# DCF_ALIM_SWITCH_RESET.net
KiCad netlist of a schematic drawn in Altium Designer
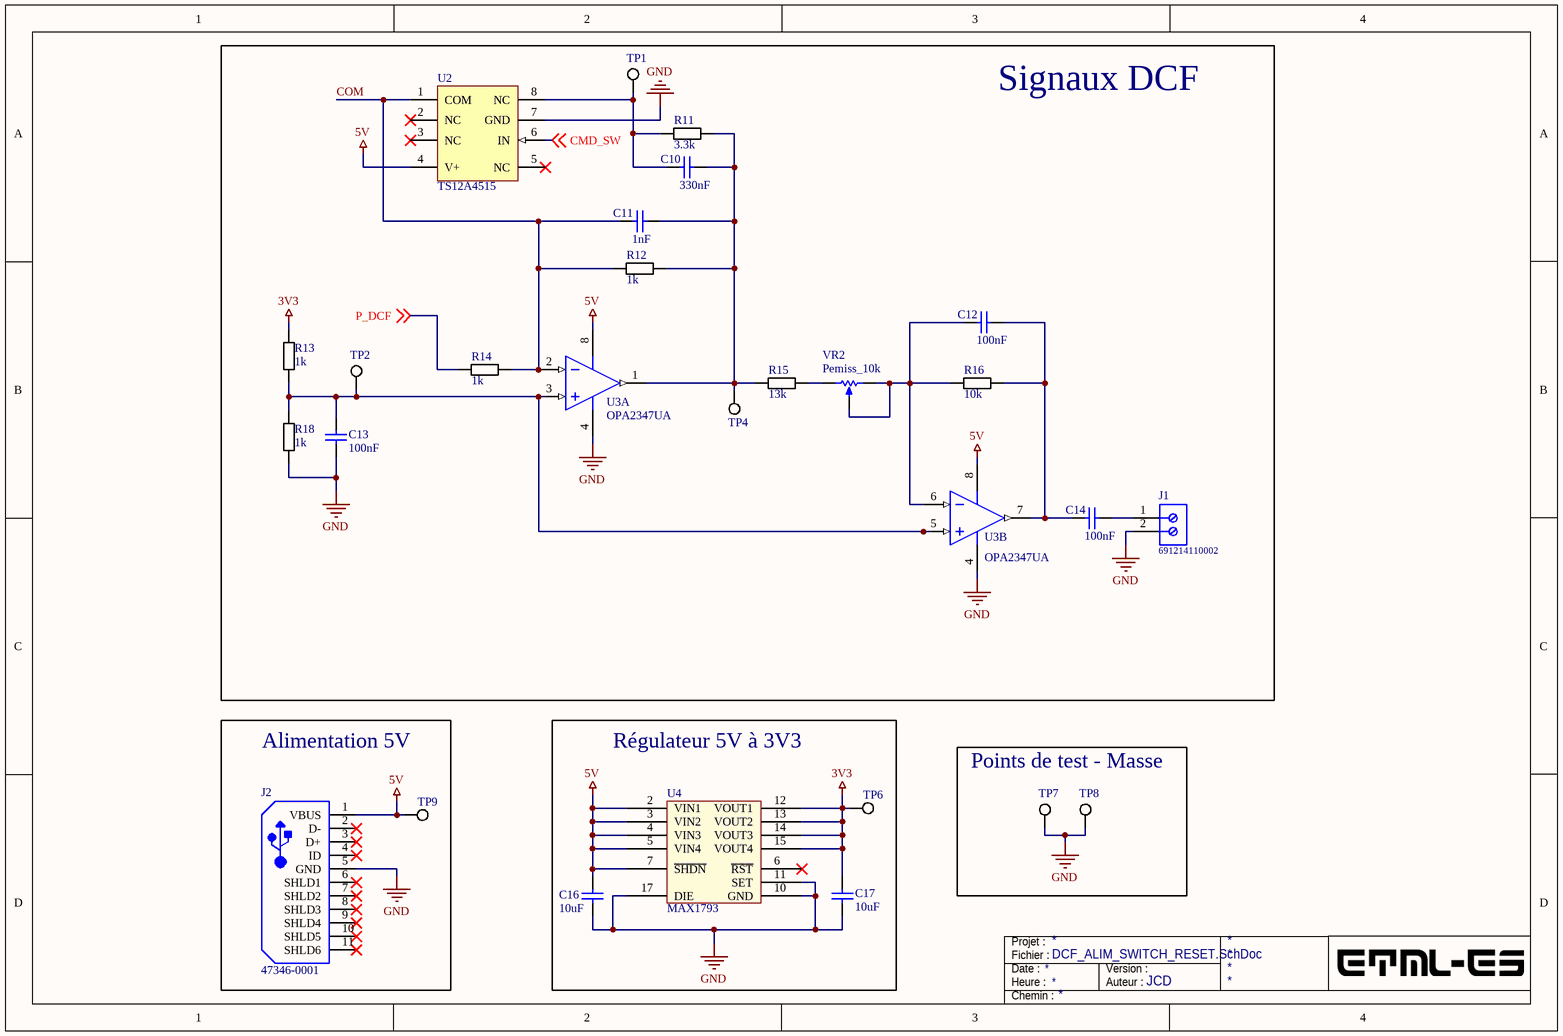
[diagram p0: DCF_ALIM_SWITCH_RESET.SchDoc]

(export (version "E")
  (design (tool "Eeschema 10.0.6"))
  (components
    (comp (ref "C10")
      (value "330nF")
      (footprint "C0805")
      (description "Capacitor")
      (fields (field (name "PUBLISHER") "Altium Limited"))
      (libsource (lib "Miscellaneous Devices") (part "Cap"))
    )
    (comp (ref "C11")
      (value "1nF")
      (footprint "C0805")
      (description "Capacitor")
      (fields (field (name "Comment") "100nF") (field (name "PUBLISHER") "Altium Limited"))
      (libsource (lib "Miscellaneous Devices") (part "Cap"))
    )
    (comp (ref "C12")
      (value "100nF")
      (footprint "C0805")
      (description "Capacitor")
      (fields (field (name "PUBLISHER") "Altium Limited"))
      (libsource (lib "Miscellaneous Devices") (part "Cap"))
    )
    (comp (ref "C13")
      (value "100nF")
      (footprint "C0805")
      (description "Capacitor")
      (fields (field (name "PUBLISHER") "Altium Limited"))
      (libsource (lib "Miscellaneous Devices") (part "Cap"))
    )
    (comp (ref "C14")
      (value "100nF")
      (footprint "C0805")
      (description "Capacitor")
      (fields (field (name "PUBLISHER") "Altium Limited"))
      (libsource (lib "Miscellaneous Devices") (part "Cap"))
    )
    (comp (ref "C16")
      (value "10uF")
      (footprint "C0805")
      (description "Capacitor")
      (fields (field (name "PUBLISHER") "Altium Limited"))
      (libsource (lib "Miscellaneous Devices") (part "Cap"))
    )
    (comp (ref "C17")
      (value "10uF")
      (footprint "C0805")
      (description "Capacitor")
      (fields (field (name "PUBLISHER") "Altium Limited"))
      (libsource (lib "Miscellaneous Devices") (part "Cap"))
    )
    (comp (ref "J1")
      (value "691214110002")
      (footprint "691214110002")
      (description "Serie 2141 - 3.50 mm Horizontal Entry Modular with Rising Cage Clamp WR-TBL, 2 pin")
      (fields (field (name "PUBLISHER") "Wurth Elektronik"))
      (libsource (lib "ALTIUM-RISING_CAGE_CLAMP_CONTBL2-rev18b") (part "691214110002"))
    )
    (comp (ref "J2")
      (value "47346-0001")
      (footprint "MOLX-47346-0001-5_V")
      (description "Micro-USB B Receptacle with Flange, -30 to 85 degC, 5-Pin SMD, RoHS, Tape and Reel")
      (fields (field (name "MANUFACTURER") "Molex"))
      (libsource (lib "Altium Content Vault") (part "MOLX-47346-0001-5"))
    )
    (comp (ref "R11")
      (value "3.3k")
      (footprint "RESC0805(2012)_L")
      (libsource (lib "") (part "Resistance_1"))
    )
    (comp (ref "R12") (value "1k") (footprint "RESC0805(2012)_L") (libsource (lib "") (part "Resistance_1")))
    (comp (ref "R13")
      (value "1k")
      (footprint "RESC0805(2012)_L")
      (libsource (lib "LibComposant1819") (part "Resistance"))
    )
    (comp (ref "R14") (value "1k") (footprint "RESC0805(2012)_L") (libsource (lib "") (part "Resistance_1")))
    (comp (ref "R15") (value "13k") (footprint "RESC0805(2012)_L") (libsource (lib "") (part "Resistance_1")))
    (comp (ref "R16") (value "10k") (footprint "RESC0805(2012)_L") (libsource (lib "") (part "Resistance_1")))
    (comp (ref "R18")
      (value "1k")
      (footprint "RESC0805(2012)_L")
      (libsource (lib "LibComposant1819") (part "Resistance"))
    )
    (comp (ref "TP1")
      (value "5019")
      (footprint "KSTN-5019_V")
      (description "Test Point, 1 Position SMD, RoHS, Tape and Reel")
      (libsource (lib "Altium Content Vault") (part "TESTPOINT_WHITE"))
    )
    (comp (ref "TP2")
      (value "5019")
      (footprint "KSTN-5019_V")
      (description "Test Point, 1 Position SMD, RoHS, Tape and Reel")
      (libsource (lib "Altium Content Vault") (part "TESTPOINT_WHITE"))
    )
    (comp (ref "TP4")
      (value "5019")
      (footprint "KSTN-5019_V")
      (description "Test Point, 1 Position SMD, RoHS, Tape and Reel")
      (libsource (lib "Altium Content Vault") (part "TESTPOINT_WHITE"))
    )
    (comp (ref "TP6")
      (value "5019")
      (footprint "KSTN-5019_V")
      (description "Test Point, 1 Position SMD, RoHS, Tape and Reel")
      (libsource (lib "Altium Content Vault") (part "TESTPOINT_WHITE"))
    )
    (comp (ref "TP7")
      (value "5019")
      (footprint "KSTN-5019_V")
      (description "Test Point, 1 Position SMD, RoHS, Tape and Reel")
      (libsource (lib "Altium Content Vault") (part "TESTPOINT_WHITE"))
    )
    (comp (ref "TP8")
      (value "5019")
      (footprint "KSTN-5019_V")
      (description "Test Point, 1 Position SMD, RoHS, Tape and Reel")
      (libsource (lib "Altium Content Vault") (part "TESTPOINT_WHITE"))
    )
    (comp (ref "TP9")
      (value "5019")
      (footprint "KSTN-5019_V")
      (description "Test Point, 1 Position SMD, RoHS, Tape and Reel")
      (libsource (lib "Altium Content Vault") (part "TESTPOINT_WHITE"))
    )
    (comp (ref "U2")
      (value "TS12A4515")
      (footprint "TI-D8_L")
      (fields (field (name "MANUFACTURER") "Texas Instruments") (field (name "PARTNUMBER") "TS12A4516D"))
      (libsource (lib "LibComposant1819") (part "TS12A4515"))
    )
    (comp (ref "U3")
      (value "OPA2347UA")
      (footprint "D0008A_M")
      (fields (field (name "MANUFACTURER") "Texas Instruments"))
      (libsource (lib "Altium Content Vault") (part "TI-OPA-8_2"))
    )
    (comp (ref "U4")
      (value "MAX1793")
      (footprint "MAX1793")
      (libsource (lib "LibComposant1819") (part "MAX1793"))
    )
    (comp (ref "VR2")
      (value "Pemiss_10k")
      (footprint "BOUR-3362P")
      (description "Square Trimpot(R) Trimming Potentiometer, 10 KOhm, 300 V, -55 to 125 degC, 3-Pin THD, RoHS, Tube")
      (fields (field (name "TOLERANCE") "1%"))
      (libsource (lib "Altium Content Vault") (part "RES-POT-3"))
    )
  )
  (nets
    (net (code "1") (name "/COM") (class "Default")
      (node (ref "C11") (pin "2") (pinfunction "2_2") (pintype "passive"))
      (node (ref "R12") (pin "1") (pinfunction "1_1") (pintype "passive"))
      (node (ref "R14") (pin "2") (pinfunction "2_2") (pintype "passive"))
      (node (ref "U2") (pin "1") (pinfunction "COM_1") (pintype "passive"))
      (node (ref "U3") (pin "2") (pinfunction "IN_A-_2") (pintype "input"))
    )
    (net (code "2") (name "3V3") (class "Default")
      (node (ref "C17") (pin "2") (pinfunction "2_2") (pintype "passive"))
      (node (ref "R13") (pin "1") (pinfunction "1_1") (pintype "passive"))
      (node (ref "TP6") (pin "1") (pinfunction "1_1") (pintype "passive"))
      (node (ref "U4") (pin "12") (pinfunction "VOUT1_12") (pintype "passive"))
      (node (ref "U4") (pin "13") (pinfunction "VOUT2_13") (pintype "passive"))
      (node (ref "U4") (pin "14") (pinfunction "VOUT3_14") (pintype "passive"))
      (node (ref "U4") (pin "15") (pinfunction "VOUT4_15") (pintype "passive"))
    )
    (net (code "3") (name "5V") (class "Default")
      (node (ref "C16") (pin "2") (pinfunction "2_2") (pintype "passive"))
      (node (ref "J2") (pin "1") (pinfunction "VBUS_1") (pintype "passive"))
      (node (ref "TP9") (pin "1") (pinfunction "1_1") (pintype "passive"))
      (node (ref "U2") (pin "4") (pinfunction "V+_4") (pintype "power_in"))
      (node (ref "U3") (pin "8") (pinfunction "V+_8") (pintype "power_in"))
      (node (ref "U4") (pin "2") (pinfunction "VIN1_2") (pintype "passive"))
      (node (ref "U4") (pin "3") (pinfunction "VIN2_3") (pintype "passive"))
      (node (ref "U4") (pin "4") (pinfunction "VIN3_4") (pintype "passive"))
      (node (ref "U4") (pin "5") (pinfunction "VIN4_5") (pintype "passive"))
      (node (ref "U4") (pin "7") (pinfunction "~{SHDN}_7") (pintype "passive"))
    )
    (net (code "4") (name "CMD_SW") (class "Default")
      (node (ref "U2") (pin "6") (pinfunction "IN_6") (pintype "input"))
    )
    (net (code "5") (name "GND") (class "Default")
      (node (ref "C13") (pin "1") (pinfunction "1_1") (pintype "passive"))
      (node (ref "C16") (pin "1") (pinfunction "1_1") (pintype "passive"))
      (node (ref "C17") (pin "1") (pinfunction "1_1") (pintype "passive"))
      (node (ref "J1") (pin "2") (pinfunction "2_2") (pintype "passive"))
      (node (ref "J2") (pin "5") (pinfunction "GND_5") (pintype "passive"))
      (node (ref "R18") (pin "2") (pinfunction "2_2") (pintype "passive"))
      (node (ref "TP7") (pin "1") (pinfunction "1_1") (pintype "passive"))
      (node (ref "TP8") (pin "1") (pinfunction "1_1") (pintype "passive"))
      (node (ref "U2") (pin "7") (pinfunction "GND_7") (pintype "power_in"))
      (node (ref "U3") (pin "4") (pinfunction "V-_4") (pintype "power_in"))
      (node (ref "U4") (pin "10") (pinfunction "GND_10") (pintype "passive"))
      (node (ref "U4") (pin "11") (pinfunction "SET_11") (pintype "passive"))
      (node (ref "U4") (pin "17") (pinfunction "DIE_17") (pintype "passive"))
    )
    (net (code "6") (name "Net-(C10-Pad2)") (class "Default")
      (node (ref "C10") (pin "2") (pinfunction "2_2") (pintype "passive"))
      (node (ref "R11") (pin "1") (pinfunction "1_1") (pintype "passive"))
      (node (ref "TP1") (pin "1") (pinfunction "1_1") (pintype "passive"))
      (node (ref "U2") (pin "8") (pinfunction "NC_8") (pintype "passive"))
    )
    (net (code "7") (name "Net-(C14-Pad1)") (class "Default")
      (node (ref "C14") (pin "1") (pinfunction "1_1") (pintype "passive"))
      (node (ref "J1") (pin "1") (pinfunction "1_1") (pintype "passive"))
    )
    (net (code "8") (name "Net-(U3A-IN_A+)") (class "Default")
      (node (ref "C13") (pin "2") (pinfunction "2_2") (pintype "passive"))
      (node (ref "R13") (pin "2") (pinfunction "2_2") (pintype "passive"))
      (node (ref "R18") (pin "1") (pinfunction "1_1") (pintype "passive"))
      (node (ref "TP2") (pin "1") (pinfunction "1_1") (pintype "passive"))
      (node (ref "U3") (pin "3") (pinfunction "IN_A+_3") (pintype "input"))
      (node (ref "U3") (pin "5") (pinfunction "IN_B+_5") (pintype "input"))
    )
    (net (code "9") (name "Net-(U3A-OUT_A)") (class "Default")
      (node (ref "C10") (pin "1") (pinfunction "1_1") (pintype "passive"))
      (node (ref "C11") (pin "1") (pinfunction "1_1") (pintype "passive"))
      (node (ref "R11") (pin "2") (pinfunction "2_2") (pintype "passive"))
      (node (ref "R12") (pin "2") (pinfunction "2_2") (pintype "passive"))
      (node (ref "R15") (pin "1") (pinfunction "1_1") (pintype "passive"))
      (node (ref "TP4") (pin "1") (pinfunction "1_1") (pintype "passive"))
      (node (ref "U3") (pin "1") (pinfunction "OUT_A_1") (pintype "output"))
    )
    (net (code "10") (name "Net-(U3B-IN_B-)") (class "Default")
      (node (ref "C12") (pin "2") (pinfunction "2_2") (pintype "passive"))
      (node (ref "R16") (pin "1") (pinfunction "1_1") (pintype "passive"))
      (node (ref "U3") (pin "6") (pinfunction "IN_B-_6") (pintype "input"))
      (node (ref "VR2") (pin "2") (pinfunction "S_2") (pintype "passive"))
      (node (ref "VR2") (pin "3") (pinfunction "CW_3") (pintype "passive"))
    )
    (net (code "11") (name "Net-(U3B-OUT_B)") (class "Default")
      (node (ref "C12") (pin "1") (pinfunction "1_1") (pintype "passive"))
      (node (ref "C14") (pin "2") (pinfunction "2_2") (pintype "passive"))
      (node (ref "R16") (pin "2") (pinfunction "2_2") (pintype "passive"))
      (node (ref "U3") (pin "7") (pinfunction "OUT_B_7") (pintype "output"))
    )
    (net (code "12") (name "Net-(VR2-CCW)") (class "Default")
      (node (ref "R15") (pin "2") (pinfunction "2_2") (pintype "passive"))
      (node (ref "VR2") (pin "1") (pinfunction "CCW_1") (pintype "passive"))
    )
    (net (code "13") (name "P_DCF") (class "Default")
      (node (ref "R14") (pin "1") (pinfunction "1_1") (pintype "passive"))
    )
    (net (code "14") (name "unconnected-(J2-D+-Pad3)") (class "Default")
      (node (ref "J2") (pin "3") (pinfunction "D+_3") (pintype "passive+no_connect"))
    )
    (net (code "15") (name "unconnected-(J2-D--Pad2)") (class "Default")
      (node (ref "J2") (pin "2") (pinfunction "D-_2") (pintype "passive+no_connect"))
    )
    (net (code "16") (name "unconnected-(J2-ID-Pad4)") (class "Default")
      (node (ref "J2") (pin "4") (pinfunction "ID_4") (pintype "passive+no_connect"))
    )
    (net (code "17") (name "unconnected-(J2-SHLD1-Pad6)") (class "Default")
      (node (ref "J2") (pin "6") (pinfunction "SHLD1_6") (pintype "passive+no_connect"))
    )
    (net (code "18") (name "unconnected-(J2-SHLD2-Pad7)") (class "Default")
      (node (ref "J2") (pin "7") (pinfunction "SHLD2_7") (pintype "passive+no_connect"))
    )
    (net (code "19") (name "unconnected-(J2-SHLD3-Pad8)") (class "Default")
      (node (ref "J2") (pin "8") (pinfunction "SHLD3_8") (pintype "passive+no_connect"))
    )
    (net (code "20") (name "unconnected-(J2-SHLD4-Pad9)") (class "Default")
      (node (ref "J2") (pin "9") (pinfunction "SHLD4_9") (pintype "passive+no_connect"))
    )
    (net (code "21") (name "unconnected-(J2-SHLD5-Pad10)") (class "Default")
      (node (ref "J2") (pin "10") (pinfunction "SHLD5_10") (pintype "passive+no_connect"))
    )
    (net (code "22") (name "unconnected-(J2-SHLD6-Pad11)") (class "Default")
      (node (ref "J2") (pin "11") (pinfunction "SHLD6_11") (pintype "passive+no_connect"))
    )
    (net (code "23") (name "unconnected-(U2-NC-Pad2)") (class "Default")
      (node (ref "U2") (pin "2") (pinfunction "NC_2") (pintype "passive+no_connect"))
    )
    (net (code "24") (name "unconnected-(U2-NC-Pad3)") (class "Default")
      (node (ref "U2") (pin "3") (pinfunction "NC_3") (pintype "passive+no_connect"))
    )
    (net (code "25") (name "unconnected-(U2-NC-Pad5)") (class "Default")
      (node (ref "U2") (pin "5") (pinfunction "NC_5") (pintype "passive+no_connect"))
    )
    (net (code "26") (name "unconnected-(U4-~{RST}-Pad6)") (class "Default")
      (node (ref "U4") (pin "6") (pinfunction "~{RST}_6") (pintype "passive+no_connect"))
    )
  )
)
